# ESP8266-01.net
KiCad netlist of a schematic drawn in EAGLE
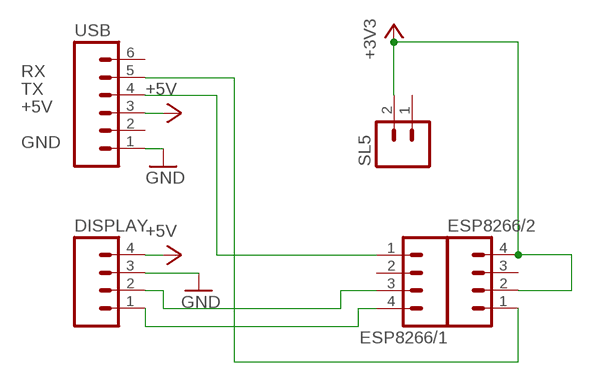
[diagram p0: schematic, sheet 1]

(export (version "E")
  (design (tool "Eeschema 10.0.6"))
  (components
    (comp (ref "DISPLAY")
      (value "M04")
      (footprint "eagle-import:04P")
      (libsource (lib "eagle-import") (part "M04"))
    )
    (comp (ref "ESP8266/1")
      (value "M04")
      (footprint "eagle-import:04P")
      (libsource (lib "eagle-import") (part "M04"))
    )
    (comp (ref "ESP8266/2")
      (value "M04")
      (footprint "eagle-import:04P")
      (libsource (lib "eagle-import") (part "M04"))
    )
    (comp (ref "SL5")
      (value "M02")
      (footprint "eagle-import:02P")
      (libsource (lib "eagle-import") (part "M02"))
    )
    (comp (ref "USB")
      (value "M06")
      (footprint "eagle-import:06P")
      (libsource (lib "eagle-import") (part "M06"))
    )
  )
  (nets
    (net (code "1") (name "+3V3") (class "Default")
      (node (ref "ESP8266/2") (pin "2") (pinfunction "2_2") (pintype "passive"))
      (node (ref "ESP8266/2") (pin "4") (pinfunction "4_4") (pintype "passive"))
      (node (ref "SL5") (pin "2") (pinfunction "2_2") (pintype "passive"))
    )
    (net (code "2") (name "+5V") (class "Default")
      (node (ref "DISPLAY") (pin "4") (pinfunction "4_4") (pintype "passive"))
      (node (ref "USB") (pin "3") (pinfunction "3_3") (pintype "passive"))
    )
    (net (code "3") (name "/RX") (class "Default")
      (node (ref "ESP8266/2") (pin "1") (pinfunction "1_1") (pintype "passive"))
      (node (ref "USB") (pin "5") (pinfunction "5_5") (pintype "passive"))
    )
    (net (code "4") (name "/TX") (class "Default")
      (node (ref "ESP8266/1") (pin "1") (pinfunction "1_1") (pintype "passive"))
      (node (ref "USB") (pin "4") (pinfunction "4_4") (pintype "passive"))
    )
    (net (code "5") (name "GND") (class "Default")
      (node (ref "DISPLAY") (pin "3") (pinfunction "3_3") (pintype "passive"))
      (node (ref "USB") (pin "1") (pinfunction "1_1") (pintype "passive"))
    )
    (net (code "6") (name "Net-(DISPLAY-Pad1)") (class "Default")
      (node (ref "DISPLAY") (pin "1") (pinfunction "1_1") (pintype "passive"))
      (node (ref "ESP8266/1") (pin "4") (pinfunction "4_4") (pintype "passive"))
    )
    (net (code "7") (name "Net-(DISPLAY-Pad2)") (class "Default")
      (node (ref "DISPLAY") (pin "2") (pinfunction "2_2") (pintype "passive"))
      (node (ref "ESP8266/1") (pin "3") (pinfunction "3_3") (pintype "passive"))
    )
    (net (code "8") (name "unconnected-(ESP8266/1-Pad2)") (class "Default")
      (node (ref "ESP8266/1") (pin "2") (pinfunction "2_2") (pintype "passive"))
    )
    (net (code "9") (name "unconnected-(ESP8266/2-Pad3)") (class "Default")
      (node (ref "ESP8266/2") (pin "3") (pinfunction "3_3") (pintype "passive"))
    )
    (net (code "10") (name "unconnected-(SL5-Pad1)") (class "Default")
      (node (ref "SL5") (pin "1") (pinfunction "1_1") (pintype "passive"))
    )
    (net (code "11") (name "unconnected-(USB-Pad2)") (class "Default")
      (node (ref "USB") (pin "2") (pinfunction "2_2") (pintype "passive"))
    )
    (net (code "12") (name "unconnected-(USB-Pad6)") (class "Default")
      (node (ref "USB") (pin "6") (pinfunction "6_6") (pintype "passive"))
    )
  )
)
